# WX0_007_418DL.net
KiCad netlist of a schematic drawn in Altium Designer
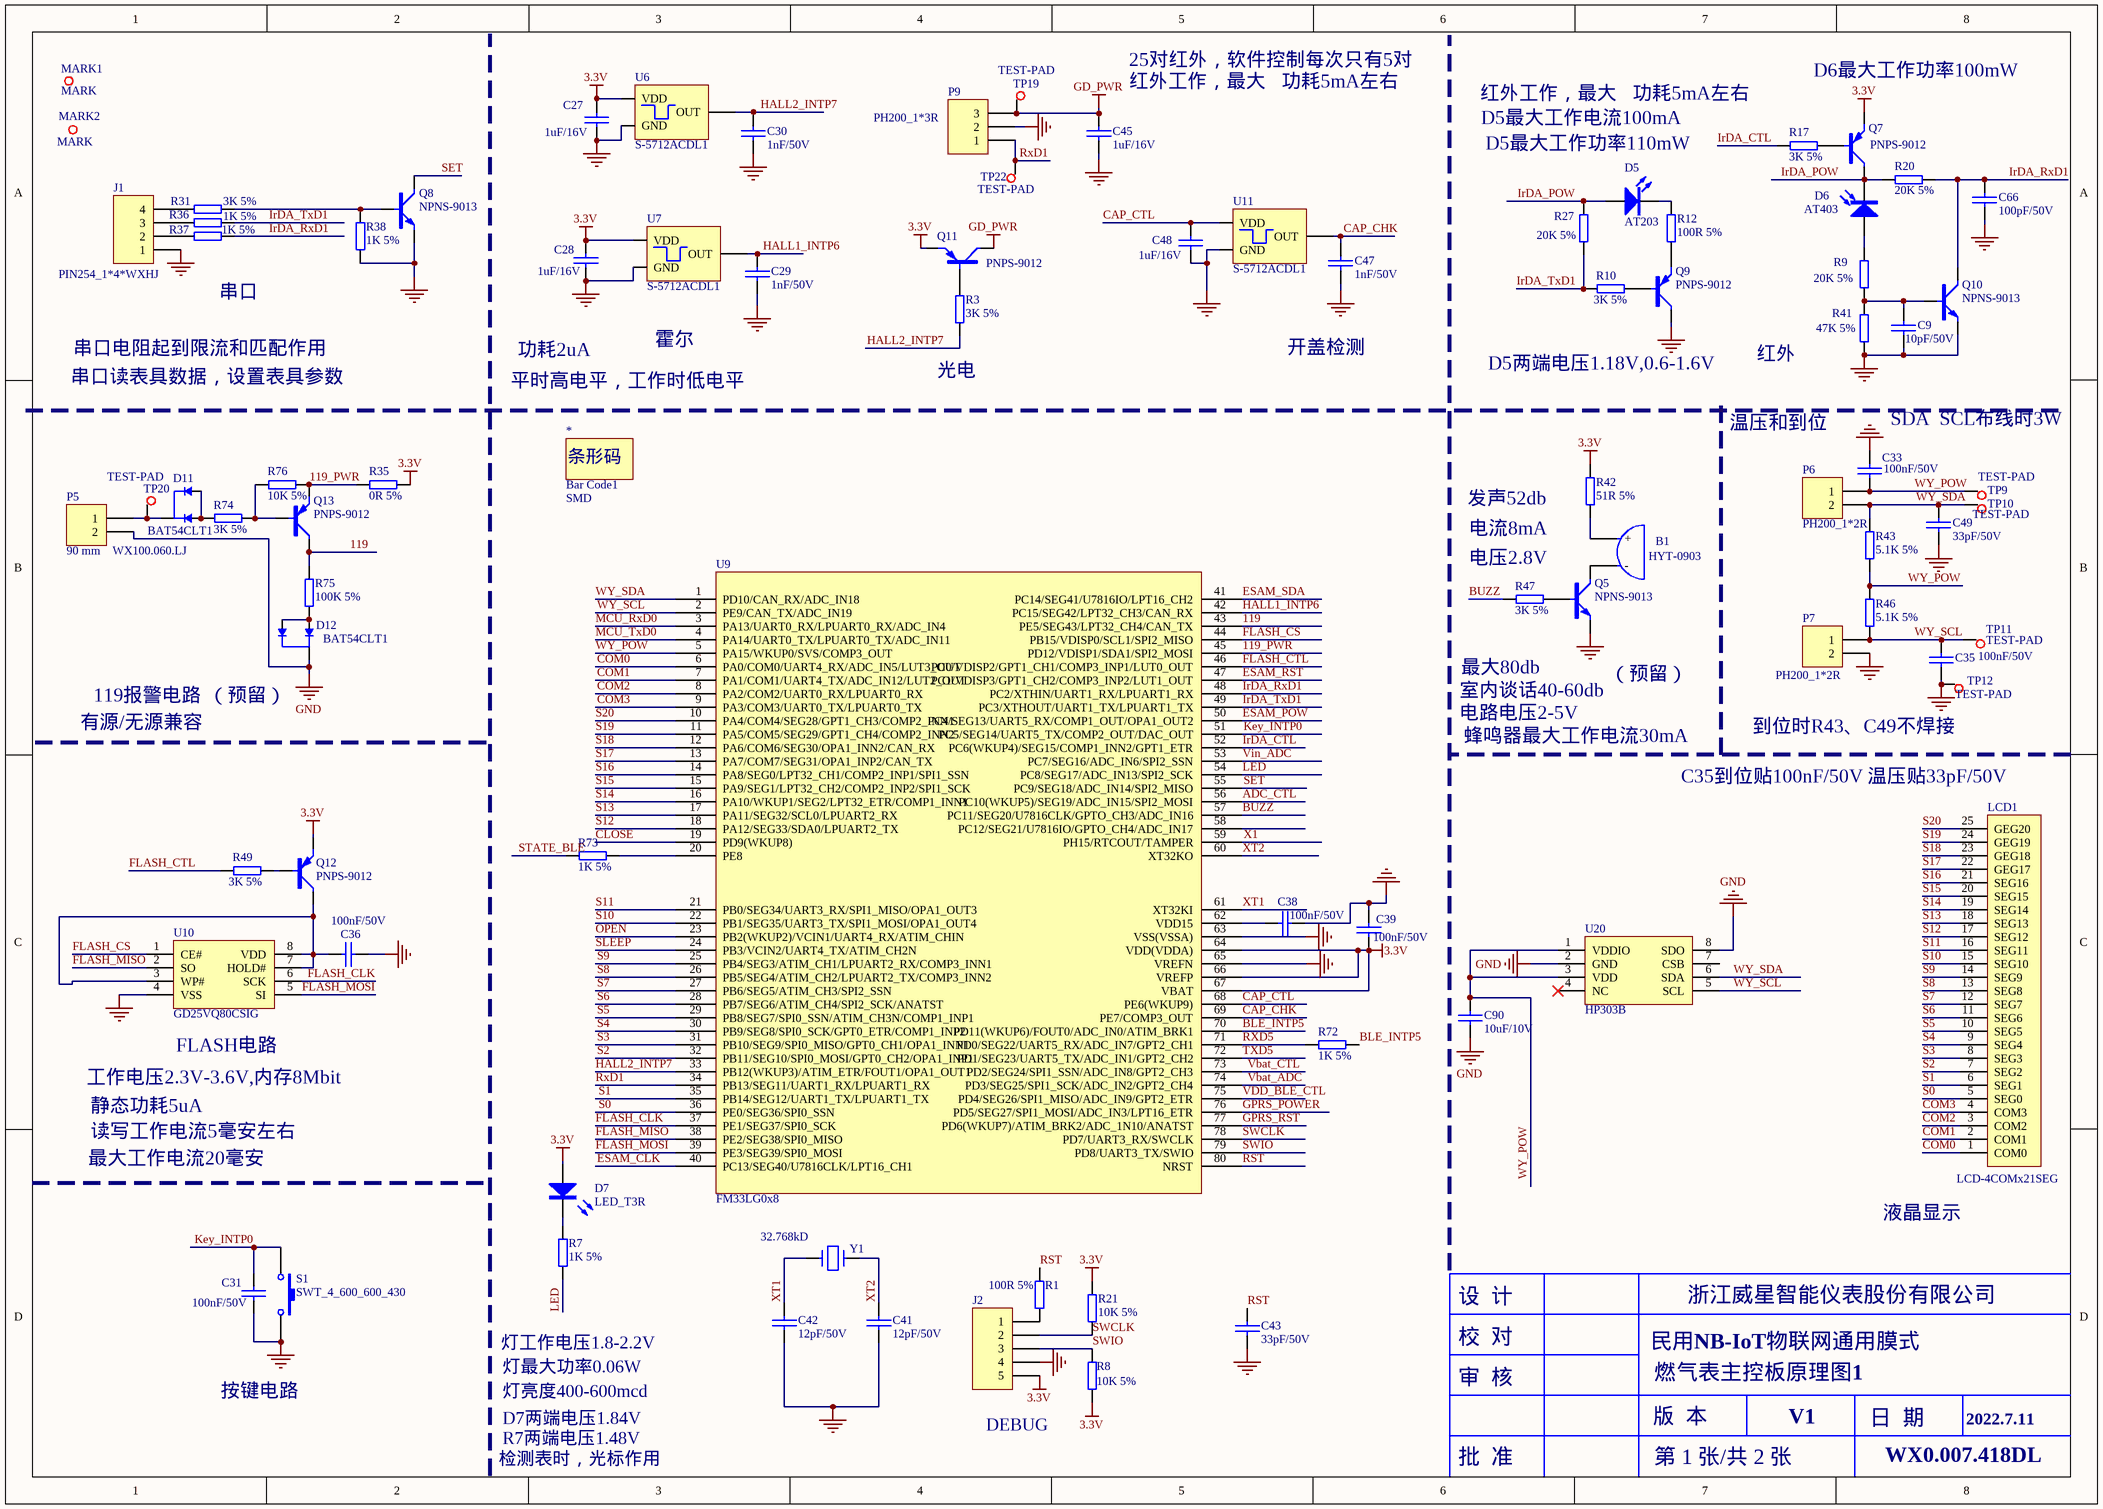
[diagram p0: WX0.007.418DL.SchDoc]

(export (version "E")
  (design (tool "Eeschema 10.0.6"))
  (components
    (comp (ref "*")
      (value "Bar Code1")
      (footprint "Bar Code1")
      (description "条形码 ,填充，无需焊接器件")
      (fields (field (name "PART NUMBER") "AD_WXHJ_Bar Code_02") (field (name "SMD/DIP") "SMD"))
      (libsource (lib "Database_Libs2") (part "05_AD_WXHJ_Bar Code_02"))
    )
    (comp (ref "B1")
      (value "HYT-0903")
      (footprint "HYT-0903")
      (description "直插,直径9mm,高5.5mm,5 V,2 V,30 mA,兴化市华宇电子有限公司,HYT-0903")
      (fields (field (name "PART NUMBER") "1010602-0007"))
      (libsource (lib "Database_Libs2") (part "07_HYT-0903"))
    )
    (comp (ref "C9")
      (value "10pF/50V")
      (footprint "CAP0603")
      (description "10pF,50 V,±5%,0603,X7R,国巨,CC0603JRNPO9BN100")
      (fields (field (name "PART NUMBER") "101020103-0014"))
      (libsource (lib "Database_Libs2") (part "CC03JPO9_10P"))
    )
    (comp (ref "C27")
      (value "1uF/16V")
      (footprint "CAP0603")
      (description "105pF,16 V,±10%,0603,国巨,CC0603KRX7R7BB105")
      (fields (field (name "PART NUMBER") "101020103-0003"))
      (libsource (lib "Database_Libs2") (part "CC03K7R7_1U"))
    )
    (comp (ref "C28")
      (value "1uF/16V")
      (footprint "CAP0603")
      (description "105pF,16 V,±10%,0603,国巨,CC0603KRX7R7BB105")
      (fields (field (name "PART NUMBER") "101020103-0003"))
      (libsource (lib "Database_Libs2") (part "CC03K7R7_1U"))
    )
    (comp (ref "C29")
      (value "1nF/50V")
      (footprint "CAP0603")
      (description "102pF,50 V,±10%,0603,国巨,CC0603KRX7R9BB102")
      (fields (field (name "PART NUMBER") "101020103-0022"))
      (libsource (lib "Database_Libs2") (part "CC03K7R9_1N"))
    )
    (comp (ref "C30")
      (value "1nF/50V")
      (footprint "CAP0603")
      (description "102pF,50 V,±10%,0603,国巨,CC0603KRX7R9BB102")
      (fields (field (name "PART NUMBER") "101020103-0022"))
      (libsource (lib "Database_Libs2") (part "CC03K7R9_1N"))
    )
    (comp (ref "C31")
      (value "100nF/50V")
      (footprint "CAP0603")
      (description "104pF,50 V,±10%,0603,国巨,CC0603KRX7R9BB104")
      (fields (field (name "PART NUMBER") "101020103-0021"))
      (libsource (lib "Database_Libs2") (part "CC03K7R9_100N"))
    )
    (comp (ref "C33")
      (value "100nF/50V")
      (footprint "CAP0603")
      (description "104pF,50 V,±10%,0603,国巨,CC0603KRX7R9BB104")
      (fields (field (name "PART NUMBER") "101020103-0021"))
      (libsource (lib "Database_Libs2") (part "CC03K7R9_100N"))
    )
    (comp (ref "C35")
      (value "100nF/50V")
      (footprint "CAP0603")
      (description "104pF,50 V,±10%,0603,国巨,CC0603KRX7R9BB104")
      (fields (field (name "PART NUMBER") "101020103-0021"))
      (libsource (lib "Database_Libs2") (part "CC03K7R9_100N"))
    )
    (comp (ref "C36")
      (value "100nF/50V")
      (footprint "CAP0603")
      (description "104pF,50 V,±10%,0603,国巨,CC0603KRX7R9BB104")
      (fields (field (name "PART NUMBER") "101020103-0021"))
      (libsource (lib "Database_Libs2") (part "CC03K7R9_100N"))
    )
    (comp (ref "C38")
      (value "100nF/50V")
      (footprint "CAP0603")
      (description "104pF,50 V,±10%,0603,国巨,CC0603KRX7R9BB104")
      (fields (field (name "PART NUMBER") "101020103-0021"))
      (libsource (lib "Database_Libs2") (part "CC03K7R9_100N"))
    )
    (comp (ref "C39")
      (value "100nF/50V")
      (footprint "CAP0603")
      (description "104pF,50 V,±10%,0603,国巨,CC0603KRX7R9BB104")
      (fields (field (name "PART NUMBER") "101020103-0021"))
      (libsource (lib "Database_Libs2") (part "CC03K7R9_100N"))
    )
    (comp (ref "C41")
      (value "12pF/50V")
      (footprint "CAP0603")
      (description "12P,50 V,±5%,0603,国巨,CC0603JRNPO9BN12")
      (fields (field (name "PART NUMBER") "101020103-0005"))
      (libsource (lib "Database_Libs2") (part "CC03JPO9_12P"))
    )
    (comp (ref "C42")
      (value "12pF/50V")
      (footprint "CAP0603")
      (description "12P,50 V,±5%,0603,国巨,CC0603JRNPO9BN12")
      (fields (field (name "PART NUMBER") "101020103-0005"))
      (libsource (lib "Database_Libs2") (part "CC03JPO9_12P"))
    )
    (comp (ref "C43")
      (value "33pF/50V")
      (footprint "CAP0603")
      (description "33pF,50 V,±10%,0603,国巨,CC0603KRNPO9BN33")
      (fields (field (name "PART NUMBER") "101020103-0027"))
      (libsource (lib "Database_Libs2") (part "CC03KPO9_33P"))
    )
    (comp (ref "C45")
      (value "1uF/16V")
      (footprint "CAP0603")
      (description "105pF,16 V,±10%,0603,国巨,CC0603KRX7R7BB105")
      (fields (field (name "PART NUMBER") "101020103-0003"))
      (libsource (lib "Database_Libs2") (part "CC03K7R7_1U"))
    )
    (comp (ref "C47")
      (value "1nF/50V")
      (footprint "CAP0603")
      (description "102pF,50 V,±10%,0603,国巨,CC0603KRX7R9BB102")
      (fields (field (name "PART NUMBER") "101020103-0022"))
      (libsource (lib "Database_Libs2") (part "CC03K7R9_1N"))
    )
    (comp (ref "C48")
      (value "1uF/16V")
      (footprint "CAP0603")
      (description "105pF,16 V,±10%,0603,国巨,CC0603KRX7R7BB105")
      (fields (field (name "PART NUMBER") "101020103-0003"))
      (libsource (lib "Database_Libs2") (part "CC03K7R7_1U"))
    )
    (comp (ref "C49")
      (value "33pF/50V")
      (footprint "CAP0603")
      (description "33pF,50 V,±10%,0603,国巨,CC0603KRNPO9BN33")
      (fields (field (name "PART NUMBER") "101020103-0027"))
      (libsource (lib "Database_Libs2") (part "CC03KPO9_33P"))
    )
    (comp (ref "C66")
      (value "100pF/50V")
      (footprint "CAP0603")
      (description "101pf,50 V,±5%,0603,国巨,CC0603JRNP09BN101")
      (fields (field (name "PART NUMBER") "101020103-0010"))
      (libsource (lib "Database_Libs2") (part "CC03JPO9_101P"))
    )
    (comp (ref "C90")
      (value "10uF/10V")
      (footprint "CAP0603")
      (description "106pF,10 V,±10%,0603,村田,GRM188R61A106KE47D")
      (fields (field (name "PART NUMBER") "101020103-0026"))
      (libsource (lib "Database_Libs2") (part "CC03K5R6_10U"))
    )
    (comp (ref "D5")
      (value "AT203")
      (footprint "IR_254_532_300")
      (description "DIP-2,φ3,插件,红光,上海品观电子有限公司/可得,AT203")
      (fields (field (name "PART NUMBER") "101040102-0010"))
      (libsource (lib "Database_Libs2") (part "01_AT203"))
    )
    (comp (ref "D6")
      (value "AT403")
      (footprint "IR_254_532_300")
      (description "DIP-2,φ3,插件,红光,上海品观电子有限公司/可得,AT403-PD-01")
      (fields (field (name "PART NUMBER") "101040102-0011"))
      (libsource (lib "Database_Libs2") (part "01_AT403"))
    )
    (comp (ref "D7")
      (value "LED_T3R")
      (footprint "LED2_300")
      (description "圆形插件,3mm 圆形,插件,红光,湖北匡通电子有限公司,3BB4HC")
      (fields (field (name "PART NUMBER") "101040102-0001"))
      (libsource (lib "Database_Libs2") (part "01-LED_T3R"))
    )
    (comp (ref "D11")
      (value "BAT54CLT1")
      (footprint "SOT-23")
      (description "BAT54CLT1，SOT23-3,SOT23-3,0.2 A,0.8 V,30 V,安森美,BAT54CLT1")
      (fields (field (name "PART NUMBER") "101040101-0038"))
      (libsource (lib "Database_Libs2") (part "02_BAT54CLT1"))
    )
    (comp (ref "D12")
      (value "BAT54CLT1")
      (footprint "SOT-23")
      (description "BAT54CLT1，SOT23-3,SOT23-3,0.2 A,0.8 V,30 V,安森美,BAT54CLT1")
      (fields (field (name "PART NUMBER") "101040101-0038"))
      (libsource (lib "Database_Libs2") (part "02_BAT54CLT1"))
    )
    (comp (ref "J1")
      (value "PIN254_1*4*WXHJ")
      (footprint "PIN254_1*4*WXHJ")
      (description "1*4 ，Φ1.0 ，2.54mm，直脚,无需焊接器件")
      (fields (field (name "PART NUMBER") "AD_WXHJ_PinHeader_01"))
      (libsource (lib "Database_Libs2") (part "PIN254_1*4*WXHJ"))
    )
    (comp (ref "J2")
      (value "PIN254_1*5*WXHJ")
      (footprint "PIN254_1*5*WXHJ")
      (description "1*5 ，Φ1.0 ，2.54mm，直脚,无需焊接器件")
      (fields (field (name "PART NUMBER") "AD_WXHJ_PinHeader_02"))
      (libsource (lib "Database_Libs2") (part "PIN254_1*5*WXHJ"))
    )
    (comp (ref "LCD1")
      (value "GVH26634A-HPP")
      (footprint "LCD_GVH21861A-HPP")
      (description "GVH26634A-HPP-WG,65mm*23mm,针脚,段码,21,液晶,全透,70 ℃,-20 ℃,安徽金视界光电科技有限公司,GVH26634A-HPP-WG")
      (fields (field (name "PART NUMBER") "1010801-0055") (field (name "SMD/DIP") "LCD-4COMx21SEG"))
      (libsource (lib "Database_Libs2") (part "03_LCD_GVH26634A-HPP"))
    )
    (comp (ref "MARK1")
      (value "MARK")
      (footprint "MARK")
      (description "MARK点")
      (fields (field (name "PART NUMBER") "AD_WXHJ_MARK_01"))
      (libsource (lib "Database_Libs2") (part "MARK"))
    )
    (comp (ref "MARK2")
      (value "MARK")
      (footprint "MARK")
      (description "MARK点")
      (fields (field (name "PART NUMBER") "AD_WXHJ_MARK_01"))
      (libsource (lib "Database_Libs2") (part "MARK"))
    )
    (comp (ref "P5")
      (value "90 mm    WX100.060.LJ")
      (footprint "WXHJ_Connect_01")
      (description "电源连接线")
      (fields (field (name "PART NUMBER") "AD_WXHJ_Connect_01"))
      (libsource (lib "Database_Libs2") (part "WXHJ_Connect_01"))
    )
    (comp (ref "P6")
      (value "PH200_1*2R")
      (footprint "PH200_1*2R")
      (description "2.0-2AW,直插弯座，2PIN，脚间距2mm，带防翘起,公头,单排,2.0-2AW;直插弯座，2PIN,脚间距2mm，带防翘起")
      (fields (field (name "PART NUMBER") "1010902-0105"))
      (libsource (lib "Database_Libs2") (part "PH200_1*2R"))
    )
    (comp (ref "P7")
      (value "PH200_1*2R")
      (footprint "PH200_1*2R")
      (description "2.0-2AW,直插弯座，2PIN，脚间距2mm，带防翘起,公头,单排,2.0-2AW;直插弯座，2PIN,脚间距2mm，带防翘起")
      (fields (field (name "PART NUMBER") "1010902-0105"))
      (libsource (lib "Database_Libs2") (part "PH200_1*2R"))
    )
    (comp (ref "P9")
      (value "PH200_1*3R")
      (footprint "PH200_1*3R")
      (description "2.0-3AW,3PIN，2mm脚间距,公头,单排,2.0-3AW；3PIN，脚间距2mm直插弯座带防翘起")
      (fields (field (name "PART NUMBER") "1010902-0104"))
      (libsource (lib "Database_Libs2") (part "PH200_1*3R"))
    )
    (comp (ref "Q5")
      (value "NPNS-9013")
      (footprint "SOT-23")
      (description "9013,NPN,SOT-23,长电,S9013")
      (fields (field (name "PART NUMBER") "101040201-0002"))
      (libsource (lib "Database_Libs2") (part "03_NPNS-9013"))
    )
    (comp (ref "Q7")
      (value "PNPS-9012")
      (footprint "SOT-23")
      (description "9012,PNP,SOT-23,JCET;长电,S9012")
      (fields (field (name "PART NUMBER") "101040201-0001"))
      (libsource (lib "Database_Libs2") (part "03_PNPS-9012"))
    )
    (comp (ref "Q8")
      (value "NPNS-9013")
      (footprint "SOT-23")
      (description "9013,NPN,SOT-23,长电,S9013")
      (fields (field (name "PART NUMBER") "101040201-0002"))
      (libsource (lib "Database_Libs2") (part "03_NPNS-9013"))
    )
    (comp (ref "Q9")
      (value "PNPS-9012")
      (footprint "SOT-23")
      (description "9012,PNP,SOT-23,JCET;长电,S9012")
      (fields (field (name "PART NUMBER") "101040201-0001"))
      (libsource (lib "Database_Libs2") (part "03_PNPS-9012"))
    )
    (comp (ref "Q10")
      (value "NPNS-9013")
      (footprint "SOT-23")
      (description "9013,NPN,SOT-23,长电,S9013")
      (fields (field (name "PART NUMBER") "101040201-0002"))
      (libsource (lib "Database_Libs2") (part "03_NPNS-9013"))
    )
    (comp (ref "Q11")
      (value "PNPS-9012")
      (footprint "SOT-23")
      (description "9012,PNP,SOT-23,JCET;长电,S9012")
      (fields (field (name "PART NUMBER") "101040201-0001"))
      (libsource (lib "Database_Libs2") (part "03_PNPS-9012"))
    )
    (comp (ref "Q12")
      (value "PNPS-9012")
      (footprint "SOT-23")
      (description "9012,PNP,SOT-23,JCET;长电,S9012")
      (fields (field (name "PART NUMBER") "101040201-0001"))
      (libsource (lib "Database_Libs2") (part "03_PNPS-9012"))
    )
    (comp (ref "Q13")
      (value "PNPS-9012")
      (footprint "SOT-23")
      (description "9012,PNP,SOT-23,JCET;长电,S9012")
      (fields (field (name "PART NUMBER") "101040201-0001"))
      (libsource (lib "Database_Libs2") (part "03_PNPS-9012"))
    )
    (comp (ref "R1")
      (value "100R 5%")
      (footprint "RES0603")
      (description "100R,±5%,1/10W,0603,国巨,RC0603JR-07100RL")
      (fields (field (name "PART NUMBER") "101010103-0022"))
      (libsource (lib "Database_Libs2") (part "RC03J_100R"))
    )
    (comp (ref "R3")
      (value "3K 5%")
      (footprint "RES0603")
      (description "国巨,±5%,0603,,155 ℃,-55 ℃,RC0603JR-073KL,无铅,100 ppm/℃,1/10W,,3K")
      (fields (field (name "PART NUMBER") "101010103-0006"))
      (libsource (lib "Database_Libs2") (part "RC03J_3K"))
    )
    (comp (ref "R7")
      (value "1K 5%")
      (footprint "RES0603")
      (description "1K,±5%,1/10W,0603,国巨,RC0603JR-071KL")
      (fields (field (name "PART NUMBER") "101010103-0008"))
      (libsource (lib "Database_Libs2") (part "RC03J_1K"))
    )
    (comp (ref "R8")
      (value "10K 5%")
      (footprint "RES0603")
      (description "国巨,±5%,0603,,155 ℃,-55 ℃,RC0603JR-0710KL,无铅,200 ppm/℃,1/10W,,10K")
      (fields (field (name "PART NUMBER") "101010103-0003"))
      (libsource (lib "Database_Libs2") (part "RC03J_10K"))
    )
    (comp (ref "R9")
      (value "20K 5%")
      (footprint "RES0603")
      (description "国巨,±5%,0603,,155 ℃,-55 ℃,RC0603JR-0720KL,无铅,200 ppm/℃,1/10W,,20K")
      (fields (field (name "PART NUMBER") "101010103-0004"))
      (libsource (lib "Database_Libs2") (part "RC03J_20K"))
    )
    (comp (ref "R10")
      (value "3K 5%")
      (footprint "RES0603")
      (description "国巨,±5%,0603,,155 ℃,-55 ℃,RC0603JR-073KL,无铅,100 ppm/℃,1/10W,,3K")
      (fields (field (name "PART NUMBER") "101010103-0006"))
      (libsource (lib "Database_Libs2") (part "RC03J_3K"))
    )
    (comp (ref "R12")
      (value "100R 5%")
      (footprint "RES0603")
      (description "100R,±5%,1/10W,0603,国巨,RC0603JR-07100RL")
      (fields (field (name "PART NUMBER") "101010103-0022"))
      (libsource (lib "Database_Libs2") (part "RC03J_100R"))
    )
    (comp (ref "R17")
      (value "3K 5%")
      (footprint "RES0603")
      (description "国巨,±5%,0603,,155 ℃,-55 ℃,RC0603JR-073KL,无铅,100 ppm/℃,1/10W,,3K")
      (fields (field (name "PART NUMBER") "101010103-0006"))
      (libsource (lib "Database_Libs2") (part "RC03J_3K"))
    )
    (comp (ref "R20")
      (value "20K 5%")
      (footprint "RES0603")
      (description "国巨,±5%,0603,,155 ℃,-55 ℃,RC0603JR-0720KL,无铅,200 ppm/℃,1/10W,,20K")
      (fields (field (name "PART NUMBER") "101010103-0004"))
      (libsource (lib "Database_Libs2") (part "RC03J_20K"))
    )
    (comp (ref "R21")
      (value "10K 5%")
      (footprint "RES0603")
      (description "国巨,±5%,0603,,155 ℃,-55 ℃,RC0603JR-0710KL,无铅,200 ppm/℃,1/10W,,10K")
      (fields (field (name "PART NUMBER") "101010103-0003"))
      (libsource (lib "Database_Libs2") (part "RC03J_10K"))
    )
    (comp (ref "R27")
      (value "20K 5%")
      (footprint "RES0603")
      (description "国巨,±5%,0603,,155 ℃,-55 ℃,RC0603JR-0720KL,无铅,200 ppm/℃,1/10W,,20K")
      (fields (field (name "PART NUMBER") "101010103-0004"))
      (libsource (lib "Database_Libs2") (part "RC03J_20K"))
    )
    (comp (ref "R31")
      (value "3K 5%")
      (footprint "RES0603")
      (description "国巨,±5%,0603,,155 ℃,-55 ℃,RC0603JR-073KL,无铅,100 ppm/℃,1/10W,,3K")
      (fields (field (name "PART NUMBER") "101010103-0006"))
      (libsource (lib "Database_Libs2") (part "RC03J_3K"))
    )
    (comp (ref "R35")
      (value "0R 5%")
      (footprint "RES1206")
      (description "0Ω,±5%,1/4W,1206,国巨,RC1206JR-070RL")
      (fields (field (name "PART NUMBER") "101010101-0013"))
      (libsource (lib "Database_Libs2") (part "RC06J_0R"))
    )
    (comp (ref "R36")
      (value "1K 5%")
      (footprint "RES0603")
      (description "1K,±5%,1/10W,0603,国巨,RC0603JR-071KL")
      (fields (field (name "PART NUMBER") "101010103-0008"))
      (libsource (lib "Database_Libs2") (part "RC03J_1K"))
    )
    (comp (ref "R37")
      (value "1K 5%")
      (footprint "RES0603")
      (description "1K,±5%,1/10W,0603,国巨,RC0603JR-071KL")
      (fields (field (name "PART NUMBER") "101010103-0008"))
      (libsource (lib "Database_Libs2") (part "RC03J_1K"))
    )
    (comp (ref "R38")
      (value "1K 5%")
      (footprint "RES0603")
      (description "1K,±5%,1/10W,0603,国巨,RC0603JR-071KL")
      (fields (field (name "PART NUMBER") "101010103-0008"))
      (libsource (lib "Database_Libs2") (part "RC03J_1K"))
    )
    (comp (ref "R41")
      (value "47K 5%")
      (footprint "RES0603")
      (description "47K,±5%,1/10W,0603,国巨,RC0603JR-0747KL")
      (fields (field (name "PART NUMBER") "101010103-0012"))
      (libsource (lib "Database_Libs2") (part "RC03J_47K"))
    )
    (comp (ref "R42")
      (value "51R 5%")
      (footprint "RES0603")
      (description "国巨,±5%,0603,,155 ℃,-55 ℃,RC0603JR-0751RL,无铅,100 ppm/℃,1/10W,,51欧")
      (fields (field (name "PART NUMBER") "101010103-0037"))
      (libsource (lib "Database_Libs2") (part "RC03J_51R"))
    )
    (comp (ref "R43")
      (value "5.1K 5%")
      (footprint "RES0603")
      (description "国巨,±5%,0603,,155 ℃,55 ℃,RC0603JR-075.1KL,无铅,200 ppm/℃,1/10W,,5.1k")
      (fields (field (name "PART NUMBER") "101010103-0015"))
      (libsource (lib "Database_Libs2") (part "RC03J_5.1K"))
    )
    (comp (ref "R46")
      (value "5.1K 5%")
      (footprint "RES0603")
      (description "国巨,±5%,0603,,155 ℃,55 ℃,RC0603JR-075.1KL,无铅,200 ppm/℃,1/10W,,5.1k")
      (fields (field (name "PART NUMBER") "101010103-0015"))
      (libsource (lib "Database_Libs2") (part "RC03J_5.1K"))
    )
    (comp (ref "R47")
      (value "3K 5%")
      (footprint "RES0603")
      (description "国巨,±5%,0603,,155 ℃,-55 ℃,RC0603JR-073KL,无铅,100 ppm/℃,1/10W,,3K")
      (fields (field (name "PART NUMBER") "101010103-0006"))
      (libsource (lib "Database_Libs2") (part "RC03J_3K"))
    )
    (comp (ref "R49")
      (value "3K 5%")
      (footprint "RES0603")
      (description "国巨,±5%,0603,,155 ℃,-55 ℃,RC0603JR-073KL,无铅,100 ppm/℃,1/10W,,3K")
      (fields (field (name "PART NUMBER") "101010103-0006"))
      (libsource (lib "Database_Libs2") (part "RC03J_3K"))
    )
    (comp (ref "R72")
      (value "1K 5%")
      (footprint "RES0603")
      (description "1K,±5%,1/10W,0603,国巨,RC0603JR-071KL")
      (fields (field (name "PART NUMBER") "101010103-0008"))
      (libsource (lib "Database_Libs2") (part "RC03J_1K"))
    )
    (comp (ref "R73")
      (value "1K 5%")
      (footprint "RES0603")
      (description "1K,±5%,1/10W,0603,国巨,RC0603JR-071KL")
      (fields (field (name "PART NUMBER") "101010103-0008"))
      (libsource (lib "Database_Libs2") (part "RC03J_1K"))
    )
    (comp (ref "R74")
      (value "3K 5%")
      (footprint "RES0603")
      (description "国巨,±5%,0603,,155 ℃,-55 ℃,RC0603JR-073KL,无铅,100 ppm/℃,1/10W,,3K")
      (fields (field (name "PART NUMBER") "101010103-0006"))
      (libsource (lib "Database_Libs2") (part "RC03J_3K"))
    )
    (comp (ref "R75")
      (value "100K 5%")
      (footprint "RES0603")
      (description "国巨,±5%,0603,,155 ℃,-55 ℃,RC0603JR-07100KL,无铅,100 ppm/℃,1/10W,,100K")
      (fields (field (name "PART NUMBER") "101010103-0005"))
      (libsource (lib "Database_Libs2") (part "RC03J_100K"))
    )
    (comp (ref "R76")
      (value "10K 5%")
      (footprint "RES0603")
      (description "国巨,±5%,0603,,155 ℃,-55 ℃,RC0603JR-0710KL,无铅,200 ppm/℃,1/10W,,10K")
      (fields (field (name "PART NUMBER") "101010103-0003"))
      (libsource (lib "Database_Libs2") (part "RC03J_10K"))
    )
    (comp (ref "S1")
      (value "SWT_4_600_600_430")
      (footprint "SWT_4_600_600")
      (description "TS-1102,机械轻触,6*6*4.3直插,6*6*4.3直插,乐清市羽欧电子")
      (fields (field (name "PART NUMBER") "1011001-0027"))
      (libsource (lib "Database_Libs2") (part "07_SWT_4_600_600_430"))
    )
    (comp (ref "TP9")
      (value "TEST-PAD")
      (footprint "TEST-PAD")
      (description "单面焊盘测试点")
      (fields (field (name "PART NUMBER") "AD_WXHJ_TEST-PAD_01"))
      (libsource (lib "Database_Libs2") (part "TEST-PAD"))
    )
    (comp (ref "TP10")
      (value "TEST-PAD")
      (footprint "TEST-PAD")
      (description "单面焊盘测试点")
      (fields (field (name "PART NUMBER") "AD_WXHJ_TEST-PAD_01"))
      (libsource (lib "Database_Libs2") (part "TEST-PAD"))
    )
    (comp (ref "TP11")
      (value "TEST-PAD")
      (footprint "TEST-PAD")
      (description "单面焊盘测试点")
      (fields (field (name "PART NUMBER") "AD_WXHJ_TEST-PAD_01"))
      (libsource (lib "Database_Libs2") (part "TEST-PAD"))
    )
    (comp (ref "TP12")
      (value "TEST-PAD")
      (footprint "TEST-PAD")
      (description "单面焊盘测试点")
      (fields (field (name "PART NUMBER") "AD_WXHJ_TEST-PAD_01"))
      (libsource (lib "Database_Libs2") (part "TEST-PAD"))
    )
    (comp (ref "TP19")
      (value "TEST-PAD")
      (footprint "TEST-PAD")
      (description "单面焊盘测试点")
      (fields (field (name "PART NUMBER") "AD_WXHJ_TEST-PAD_01"))
      (libsource (lib "Database_Libs2") (part "TEST-PAD"))
    )
    (comp (ref "TP20")
      (value "TEST-PAD")
      (footprint "TEST-PAD")
      (description "单面焊盘测试点")
      (fields (field (name "PART NUMBER") "AD_WXHJ_TEST-PAD_01"))
      (libsource (lib "Database_Libs2") (part "TEST-PAD"))
    )
    (comp (ref "TP22")
      (value "TEST-PAD")
      (footprint "TEST-PAD")
      (description "单面焊盘测试点")
      (fields (field (name "PART NUMBER") "AD_WXHJ_TEST-PAD_01"))
      (libsource (lib "Database_Libs2") (part "TEST-PAD"))
    )
    (comp (ref "U6")
      (value "S-5712ACDL1")
      (footprint "SOT-23")
      (description "S-5712ACDL1,SOT23-3,3.5 V,1.6 V,2 uA,精工电子,S-5712ACDL1")
      (fields (field (name "PART NUMBER") "1010504-0002"))
      (libsource (lib "Database_Libs2") (part "01_S-5712ACDL1"))
    )
    (comp (ref "U7")
      (value "S-5712ACDL1")
      (footprint "SOT-23")
      (description "S-5712ACDL1,SOT23-3,3.5 V,1.6 V,2 uA,精工电子,S-5712ACDL1")
      (fields (field (name "PART NUMBER") "1010504-0002"))
      (libsource (lib "Database_Libs2") (part "01_S-5712ACDL1"))
    )
    (comp (ref "U9") (value "FM33LG0x8") (footprint "LQFP80") (libsource (lib "FM_MCU") (part "FM33LG0x8")))
    (comp (ref "U10")
      (value "GD25VQ80CSIG")
      (footprint "SOP-8L-200MIL")
      (description "GD25VQ80CSIG,SOP8 208mil,北京兆易创新科技股份有限公司,GD25VQ80CSIG")
      (fields (field (name "PART NUMBER") "101050101-0165"))
      (libsource (lib "Database_Libs2") (part "04_GD25VQ80CSIG"))
    )
    (comp (ref "U11")
      (value "S-5712ACDL1")
      (footprint "SOT-23")
      (description "S-5712ACDL1,SOT23-3,3.5 V,1.6 V,2 uA,精工电子,S-5712ACDL1")
      (fields (field (name "PART NUMBER") "1010504-0002"))
      (libsource (lib "Database_Libs2") (part "01_S-5712ACDL1"))
    )
    (comp (ref "U20") (value "HP303B") (footprint "LGA_8") (libsource (lib "Schlib2") (part "HP303B")))
    (comp (ref "Y1")
      (value "32.768kD")
      (footprint "SMD-3215_2P")
      (fields (field (name "PART NUMBER") "1010601-0020"))
      (libsource (lib "Database_Libs2") (part "04_XTALSG12MD_32.768kD"))
    )
  )
  (nets
    (net (code "1") (name "/119") (class "Default")
      (node (ref "Q13") (pin "3") (pinfunction "C_3") (pintype "passive"))
      (node (ref "R75") (pin "2") (pinfunction "2_2") (pintype "passive"))
      (node (ref "U9") (pin "43") (pinfunction "PE5/SEG43/LPT32_CH4/CAN_TX_43") (pintype "passive"))
    )
    (net (code "2") (name "/119_PWR") (class "Default")
      (node (ref "Q13") (pin "2") (pinfunction "E_2") (pintype "passive"))
      (node (ref "R35") (pin "2") (pinfunction "2_2") (pintype "passive"))
      (node (ref "R76") (pin "1") (pinfunction "1_1") (pintype "passive"))
      (node (ref "U9") (pin "45") (pinfunction "PD12/VDISP1/SDA1/SPI2_MOSI_45") (pintype "passive"))
    )
    (net (code "3") (name "/ADC_CTL") (class "Default")
      (node (ref "U9") (pin "56") (pinfunction "PC10(WKUP5)/SEG19/ADC_IN15/SPI2_MOSI_56") (pintype "passive"))
    )
    (net (code "4") (name "/BLE_INTP5") (class "Default")
      (node (ref "R72") (pin "1") (pinfunction "1_1") (pintype "passive"))
      (node (ref "U9") (pin "70") (pinfunction "PD11(WKUP6)/FOUT0/ADC_IN0/ATIM_BRK1_70") (pintype "passive"))
    )
    (net (code "5") (name "/BUZZ") (class "Default")
      (node (ref "R47") (pin "1") (pinfunction "1_1") (pintype "passive"))
      (node (ref "U9") (pin "57") (pinfunction "PC11/SEG20/U7816CLK/GPTO_CH3/ADC_IN16_57") (pintype "passive"))
    )
    (net (code "6") (name "/CAP_CHK") (class "Default")
      (node (ref "C47") (pin "1") (pinfunction "1_1") (pintype "passive"))
      (node (ref "U11") (pin "2") (pinfunction "OUT_2") (pintype "passive"))
      (node (ref "U9") (pin "69") (pinfunction "PE7/COMP3_OUT_69") (pintype "passive"))
    )
    (net (code "7") (name "/CAP_CTL") (class "Default")
      (node (ref "C48") (pin "1") (pinfunction "1_1") (pintype "passive"))
      (node (ref "U11") (pin "1") (pinfunction "VDD_1") (pintype "passive"))
      (node (ref "U9") (pin "68") (pinfunction "PE6(WKUP9)_68") (pintype "passive"))
    )
    (net (code "8") (name "/CLOSE") (class "Default")
      (node (ref "U9") (pin "19") (pinfunction "PD9(WKUP8)_19") (pintype "passive"))
    )
    (net (code "9") (name "/COM0") (class "Default")
      (node (ref "LCD1") (pin "1") (pinfunction "COM0_1") (pintype "passive"))
      (node (ref "U9") (pin "6") (pinfunction "PA0/COM0/UART4_RX/ADC_IN5/LUT3_OUT_6") (pintype "passive"))
    )
    (net (code "10") (name "/COM1") (class "Default")
      (node (ref "LCD1") (pin "2") (pinfunction "COM1_2") (pintype "passive"))
      (node (ref "U9") (pin "7") (pinfunction "PA1/COM1/UART4_TX/ADC_IN12/LUT2_OUT_7") (pintype "passive"))
    )
    (net (code "11") (name "/COM2") (class "Default")
      (node (ref "LCD1") (pin "3") (pinfunction "COM2_3") (pintype "passive"))
      (node (ref "U9") (pin "8") (pinfunction "PA2/COM2/UART0_RX/LPUART0_RX_8") (pintype "passive"))
    )
    (net (code "12") (name "/COM3") (class "Default")
      (node (ref "LCD1") (pin "4") (pinfunction "COM3_4") (pintype "passive"))
      (node (ref "U9") (pin "9") (pinfunction "PA3/COM3/UART0_TX/LPUART0_TX_9") (pintype "passive"))
    )
    (net (code "13") (name "/ESAM_CLK") (class "Default")
      (node (ref "U9") (pin "40") (pinfunction "PC13/SEG40/U7816CLK/LPT16_CH1_40") (pintype "passive"))
    )
    (net (code "14") (name "/ESAM_POW") (class "Default")
      (node (ref "U9") (pin "50") (pinfunction "PC4/SEG13/UART5_RX/COMP1_OUT/OPA1_OUT2_50") (pintype "passive"))
    )
    (net (code "15") (name "/ESAM_RST") (class "Default")
      (node (ref "U9") (pin "47") (pinfunction "PC1/VDISP3/GPT1_CH2/COMP3_INP2/LUT1_OUT_47") (pintype "passive"))
    )
    (net (code "16") (name "/ESAM_SDA") (class "Default")
      (node (ref "U9") (pin "41") (pinfunction "PC14/SEG41/U7816IO/LPT16_CH2_41") (pintype "passive"))
    )
    (net (code "17") (name "/FLASH_CLK") (class "Default")
      (node (ref "U10") (pin "6") (pinfunction "SCK_6") (pintype "passive"))
      (node (ref "U9") (pin "37") (pinfunction "PE1/SEG37/SPI0_SCK_37") (pintype "passive"))
    )
    (net (code "18") (name "/FLASH_CS") (class "Default")
      (node (ref "U10") (pin "1") (pinfunction "CE#_1") (pintype "passive"))
      (node (ref "U9") (pin "44") (pinfunction "PB15/VDISP0/SCL1/SPI2_MISO_44") (pintype "passive"))
    )
    (net (code "19") (name "/FLASH_CTL") (class "Default")
      (node (ref "R49") (pin "1") (pinfunction "1_1") (pintype "passive"))
      (node (ref "U9") (pin "46") (pinfunction "PC0/VDISP2/GPT1_CH1/COMP3_INP1/LUT0_OUT_46") (pintype "passive"))
    )
    (net (code "20") (name "/FLASH_MISO") (class "Default")
      (node (ref "U10") (pin "2") (pinfunction "SO_2") (pintype "passive"))
      (node (ref "U9") (pin "38") (pinfunction "PE2/SEG38/SPI0_MISO_38") (pintype "passive"))
    )
    (net (code "21") (name "/FLASH_MOSI") (class "Default")
      (node (ref "U10") (pin "5") (pinfunction "SI_5") (pintype "passive"))
      (node (ref "U9") (pin "39") (pinfunction "PE3/SEG39/SPI0_MOSI_39") (pintype "passive"))
    )
    (net (code "22") (name "/GPRS_POWER") (class "Default")
      (node (ref "U9") (pin "76") (pinfunction "PD5/SEG27/SPI1_MOSI/ADC_IN3/LPT16_ETR_76") (pintype "passive"))
    )
    (net (code "23") (name "/GPRS_RST") (class "Default")
      (node (ref "U9") (pin "77") (pinfunction "PD6(WKUP7)/ATIM_BRK2/ADC_1N10/ANATST_77") (pintype "passive"))
    )
    (net (code "24") (name "/HALL1_INTP6") (class "Default")
      (node (ref "C29") (pin "1") (pinfunction "1_1") (pintype "passive"))
      (node (ref "U7") (pin "2") (pinfunction "OUT_2") (pintype "passive"))
      (node (ref "U9") (pin "42") (pinfunction "PC15/SEG42/LPT32_CH3/CAN_RX_42") (pintype "passive"))
    )
    (net (code "25") (name "/HALL2_INTP7") (class "Default")
      (node (ref "C30") (pin "1") (pinfunction "1_1") (pintype "passive"))
      (node (ref "R3") (pin "1") (pinfunction "1_1") (pintype "passive"))
      (node (ref "U6") (pin "2") (pinfunction "OUT_2") (pintype "passive"))
      (node (ref "U9") (pin "33") (pinfunction "PB12(WKUP3)/ATIM_ETR/FOUT1/OPA1_OUT1_33") (pintype "passive"))
    )
    (net (code "26") (name "/IrDA_CTL") (class "Default")
      (node (ref "R17") (pin "1") (pinfunction "1_1") (pintype "passive"))
      (node (ref "U9") (pin "52") (pinfunction "PC6(WKUP4)/SEG15/COMP1_INN2/GPT1_ETR_52") (pintype "passive"))
    )
    (net (code "27") (name "/IrDA_POW") (class "Default")
      (node (ref "D5") (pin "1") (pinfunction "A_1") (pintype "passive"))
      (node (ref "D6") (pin "2") (pinfunction "K_2") (pintype "passive"))
      (node (ref "Q7") (pin "3") (pinfunction "C_3") (pintype "passive"))
      (node (ref "R20") (pin "1") (pinfunction "1_1") (pintype "passive"))
      (node (ref "R27") (pin "2") (pinfunction "2_2") (pintype "passive"))
    )
    (net (code "28") (name "/IrDA_RxD1") (class "Default")
      (node (ref "C66") (pin "1") (pinfunction "1_1") (pintype "passive"))
      (node (ref "Q10") (pin "3") (pinfunction "C_3") (pintype "passive"))
      (node (ref "R20") (pin "2") (pinfunction "2_2") (pintype "passive"))
      (node (ref "R37") (pin "2") (pinfunction "2_2") (pintype "passive"))
      (node (ref "U9") (pin "48") (pinfunction "PC2/XTHIN/UART1_RX/LPUART1_RX_48") (pintype "passive"))
    )
    (net (code "29") (name "/IrDA_TxD1") (class "Default")
      (node (ref "R10") (pin "1") (pinfunction "1_1") (pintype "passive"))
      (node (ref "R27") (pin "1") (pinfunction "1_1") (pintype "passive"))
      (node (ref "R36") (pin "2") (pinfunction "2_2") (pintype "passive"))
      (node (ref "U9") (pin "49") (pinfunction "PC3/XTHOUT/UART1_TX/LPUART1_TX_49") (pintype "passive"))
    )
    (net (code "30") (name "/Key_INTP0") (class "Default")
      (node (ref "C31") (pin "1") (pinfunction "1_1") (pintype "passive"))
      (node (ref "S1") (pin "1") (pinfunction "1_1") (pintype "passive"))
      (node (ref "U9") (pin "51") (pinfunction "PC5/SEG14/UART5_TX/COMP2_OUT/DAC_OUT_51") (pintype "passive"))
    )
    (net (code "31") (name "/LED") (class "Default")
      (node (ref "R7") (pin "1") (pinfunction "1_1") (pintype "passive"))
      (node (ref "U9") (pin "54") (pinfunction "PC8/SEG17/ADC_IN13/SPI2_SCK_54") (pintype "passive"))
    )
    (net (code "32") (name "/MCU_RxD0") (class "Default")
      (node (ref "U9") (pin "3") (pinfunction "PA13/UART0_RX/LPUART0_RX/ADC_IN4_3") (pintype "passive"))
    )
    (net (code "33") (name "/MCU_TxD0") (class "Default")
      (node (ref "U9") (pin "4") (pinfunction "PA14/UART0_TX/LPUART0_TX/ADC_IN11_4") (pintype "passive"))
    )
    (net (code "34") (name "/OPEN") (class "Default")
      (node (ref "U9") (pin "23") (pinfunction "PB2(WKUP2)/VCIN1/UART4_RX/ATIM_CHIN_23") (pintype "passive"))
    )
    (net (code "35") (name "/RST") (class "Default")
      (node (ref "C43") (pin "1") (pinfunction "1_1") (pintype "passive"))
      (node (ref "R1") (pin "1") (pinfunction "1_1") (pintype "passive"))
      (node (ref "U9") (pin "80") (pinfunction "NRST_80") (pintype "passive"))
    )
    (net (code "36") (name "/RXD5") (class "Default")
      (node (ref "R72") (pin "2") (pinfunction "2_2") (pintype "passive"))
      (node (ref "U9") (pin "71") (pinfunction "PD0/SEG22/UART5_RX/ADC_IN7/GPT2_CH1_71") (pintype "passive"))
    )
    (net (code "37") (name "/RxD1") (class "Default")
      (node (ref "P9") (pin "1") (pinfunction "1_1") (pintype "passive"))
      (node (ref "TP22") (pin "1") (pinfunction "1_1") (pintype "passive"))
      (node (ref "U9") (pin "34") (pinfunction "PB13/SEG11/UART1_RX/LPUART1_RX_34") (pintype "passive"))
    )
    (net (code "38") (name "/S0") (class "Default")
      (node (ref "LCD1") (pin "5") (pinfunction "SEG0_5") (pintype "passive"))
      (node (ref "U9") (pin "36") (pinfunction "PE0/SEG36/SPI0_SSN_36") (pintype "passive"))
    )
    (net (code "39") (name "/S1") (class "Default")
      (node (ref "LCD1") (pin "6") (pinfunction "SEG1_6") (pintype "passive"))
      (node (ref "U9") (pin "35") (pinfunction "PB14/SEG12/UART1_TX/LPUART1_TX_35") (pintype "passive"))
    )
    (net (code "40") (name "/S2") (class "Default")
      (node (ref "LCD1") (pin "7") (pinfunction "SEG2_7") (pintype "passive"))
      (node (ref "U9") (pin "32") (pinfunction "PB11/SEG10/SPI0_MOSI/GPT0_CH2/OPA1_INP1_32") (pintype "passive"))
    )
    (net (code "41") (name "/S3") (class "Default")
      (node (ref "LCD1") (pin "8") (pinfunction "SEG3_8") (pintype "passive"))
      (node (ref "U9") (pin "31") (pinfunction "PB10/SEG9/SPI0_MISO/GPT0_CH1/OPA1_INN1_31") (pintype "passive"))
    )
    (net (code "42") (name "/S4") (class "Default")
      (node (ref "LCD1") (pin "9") (pinfunction "SEG4_9") (pintype "passive"))
      (node (ref "U9") (pin "30") (pinfunction "PB9/SEG8/SPI0_SCK/GPT0_ETR/COMP1_INP2_30") (pintype "passive"))
    )
    (net (code "43") (name "/S5") (class "Default")
      (node (ref "LCD1") (pin "10") (pinfunction "SEG5_10") (pintype "passive"))
      (node (ref "U9") (pin "29") (pinfunction "PB8/SEG7/SPI0_SSN/ATIM_CH3N/COMP1_INP1_29") (pintype "passive"))
    )
    (net (code "44") (name "/S6") (class "Default")
      (node (ref "LCD1") (pin "11") (pinfunction "SEG6_11") (pintype "passive"))
      (node (ref "U9") (pin "28") (pinfunction "PB7/SEG6/ATIM_CH4/SPI2_SCK/ANATST_28") (pintype "passive"))
    )
    (net (code "45") (name "/S7") (class "Default")
      (node (ref "LCD1") (pin "12") (pinfunction "SEG7_12") (pintype "passive"))
      (node (ref "U9") (pin "27") (pinfunction "PB6/SEG5/ATIM_CH3/SPI2_SSN_27") (pintype "passive"))
    )
    (net (code "46") (name "/S8") (class "Default")
      (node (ref "LCD1") (pin "13") (pinfunction "SEG8_13") (pintype "passive"))
      (node (ref "U9") (pin "26") (pinfunction "PB5/SEG4/ATIM_CH2/LPUART2_TX/COMP3_INN2_26") (pintype "passive"))
    )
    (net (code "47") (name "/S9") (class "Default")
      (node (ref "LCD1") (pin "14") (pinfunction "SEG9_14") (pintype "passive"))
      (node (ref "U9") (pin "25") (pinfunction "PB4/SEG3/ATIM_CH1/LPUART2_RX/COMP3_INN1_25") (pintype "passive"))
    )
    (net (code "48") (name "/S10") (class "Default")
      (node (ref "LCD1") (pin "15") (pinfunction "SEG10_15") (pintype "passive"))
      (node (ref "U9") (pin "22") (pinfunction "PB1/SEG35/UART3_TX/SPI1_MOSI/OPA1_OUT4_22") (pintype "passive"))
    )
    (net (code "49") (name "/S11") (class "Default")
      (node (ref "LCD1") (pin "16") (pinfunction "SEG11_16") (pintype "passive"))
      (node (ref "U9") (pin "21") (pinfunction "PB0/SEG34/UART3_RX/SPI1_MISO/OPA1_OUT3_21") (pintype "passive"))
    )
    (net (code "50") (name "/S12") (class "Default")
      (node (ref "LCD1") (pin "17") (pinfunction "SEG12_17") (pintype "passive"))
      (node (ref "U9") (pin "18") (pinfunction "PA12/SEG33/SDA0/LPUART2_TX_18") (pintype "passive"))
    )
    (net (code "51") (name "/S13") (class "Default")
      (node (ref "LCD1") (pin "18") (pinfunction "SEG13_18") (pintype "passive"))
      (node (ref "U9") (pin "17") (pinfunction "PA11/SEG32/SCL0/LPUART2_RX_17") (pintype "passive"))
    )
    (net (code "52") (name "/S14") (class "Default")
      (node (ref "LCD1") (pin "19") (pinfunction "SEG14_19") (pintype "passive"))
      (node (ref "U9") (pin "16") (pinfunction "PA10/WKUP1/SEG2/LPT32_ETR/COMP1_INN1_16") (pintype "passive"))
    )
    (net (code "53") (name "/S15") (class "Default")
      (node (ref "LCD1") (pin "20") (pinfunction "SEG15_20") (pintype "passive"))
      (node (ref "U9") (pin "15") (pinfunction "PA9/SEG1/LPT32_CH2/COMP2_INP2/SPI1_SCK_15") (pintype "passive"))
    )
    (net (code "54") (name "/S16") (class "Default")
      (node (ref "LCD1") (pin "21") (pinfunction "SEG16_21") (pintype "passive"))
      (node (ref "U9") (pin "14") (pinfunction "PA8/SEG0/LPT32_CH1/COMP2_INP1/SPI1_SSN_14") (pintype "passive"))
    )
    (net (code "55") (name "/S17") (class "Default")
      (node (ref "LCD1") (pin "22") (pinfunction "GEG17_22") (pintype "passive"))
      (node (ref "U9") (pin "13") (pinfunction "PA7/COM7/SEG31/OPA1_INP2/CAN_TX_13") (pintype "passive"))
    )
    (net (code "56") (name "/S18") (class "Default")
      (node (ref "LCD1") (pin "23") (pinfunction "GEG18_23") (pintype "passive"))
      (node (ref "U9") (pin "12") (pinfunction "PA6/COM6/SEG30/OPA1_INN2/CAN_RX_12") (pintype "passive"))
    )
    (net (code "57") (name "/S19") (class "Default")
      (node (ref "LCD1") (pin "24") (pinfunction "GEG19_24") (pintype "passive"))
      (node (ref "U9") (pin "11") (pinfunction "PA5/COM5/SEG29/GPT1_CH4/COMP2_INN2_11") (pintype "passive"))
    )
    (net (code "58") (name "/S20") (class "Default")
      (node (ref "LCD1") (pin "25") (pinfunction "GEG20_25") (pintype "passive"))
      (node (ref "U9") (pin "10") (pinfunction "PA4/COM4/SEG28/GPT1_CH3/COMP2_INN1_10") (pintype "passive"))
    )
    (net (code "59") (name "/SET") (class "Default")
      (node (ref "Q8") (pin "3") (pinfunction "C_3") (pintype "passive"))
      (node (ref "U9") (pin "55") (pinfunction "PC9/SEG18/ADC_IN14/SPI2_MISO_55") (pintype "passive"))
    )
    (net (code "60") (name "/SLEEP") (class "Default")
      (node (ref "U9") (pin "24") (pinfunction "PB3/VCIN2/UART4_TX/ATIM_CH2N_24") (pintype "passive"))
    )
    (net (code "61") (name "/STATE_BLE") (class "Default")
      (node (ref "R73") (pin "2") (pinfunction "2_2") (pintype "passive"))
    )
    (net (code "62") (name "/SWCLK") (class "Default")
      (node (ref "J2") (pin "2") (pinfunction "2_2") (pintype "passive"))
      (node (ref "R21") (pin "2") (pinfunction "2_2") (pintype "passive"))
      (node (ref "U9") (pin "78") (pinfunction "PD7/UART3_RX/SWCLK_78") (pintype "passive"))
    )
    (net (code "63") (name "/SWIO") (class "Default")
      (node (ref "J2") (pin "3") (pinfunction "3_3") (pintype "passive"))
      (node (ref "R8") (pin "2") (pinfunction "2_2") (pintype "passive"))
      (node (ref "U9") (pin "79") (pinfunction "PD8/UART3_TX/SWIO_79") (pintype "passive"))
    )
    (net (code "64") (name "/TXD5") (class "Default")
      (node (ref "U9") (pin "72") (pinfunction "PD1/SEG23/UART5_TX/ADC_IN1/GPT2_CH2_72") (pintype "passive"))
    )
    (net (code "65") (name "/VDD_BLE_CTL") (class "Default")
      (node (ref "U9") (pin "75") (pinfunction "PD4/SEG26/SPI1_MISO/ADC_IN9/GPT2_ETR_75") (pintype "passive"))
    )
    (net (code "66") (name "/Vbat_ADC") (class "Default")
      (node (ref "U9") (pin "74") (pinfunction "PD3/SEG25/SPI1_SCK/ADC_IN2/GPT2_CH4_74") (pintype "passive"))
    )
    (net (code "67") (name "/Vbat_CTL") (class "Default")
      (node (ref "U9") (pin "73") (pinfunction "PD2/SEG24/SPI1_SSN/ADC_IN8/GPT2_CH3_73") (pintype "passive"))
    )
    (net (code "68") (name "/Vin_ADC") (class "Default")
      (node (ref "U9") (pin "53") (pinfunction "PC7/SEG16/ADC_IN6/SPI2_SSN_53") (pintype "passive"))
    )
    (net (code "69") (name "/WY_POW") (class "Default")
      (node (ref "C33") (pin "2") (pinfunction "2_2") (pintype "passive"))
      (node (ref "C90") (pin "2") (pinfunction "2_2") (pintype "passive"))
      (node (ref "P6") (pin "1") (pinfunction "1_1") (pintype "passive"))
      (node (ref "R43") (pin "1") (pinfunction "1_1") (pintype "passive"))
      (node (ref "R46") (pin "2") (pinfunction "2_2") (pintype "passive"))
      (node (ref "TP9") (pin "1") (pinfunction "1_1") (pintype "passive"))
      (node (ref "U20") (pin "1") (pinfunction "VDDIO_1") (pintype "passive"))
      (node (ref "U20") (pin "3") (pinfunction "VDD_3") (pintype "passive"))
      (node (ref "U9") (pin "5") (pinfunction "PA15/WKUP0/SVS/COMP3_OUT_5") (pintype "passive"))
    )
    (net (code "70") (name "/WY_SCL") (class "Default")
      (node (ref "C35") (pin "1") (pinfunction "1_1") (pintype "passive"))
      (node (ref "P7") (pin "1") (pinfunction "1_1") (pintype "passive"))
      (node (ref "R46") (pin "1") (pinfunction "1_1") (pintype "passive"))
      (node (ref "TP11") (pin "1") (pinfunction "1_1") (pintype "passive"))
      (node (ref "U20") (pin "5") (pinfunction "SCL_5") (pintype "passive"))
      (node (ref "U9") (pin "2") (pinfunction "PE9/CAN_TX/ADC_IN19_2") (pintype "passive"))
    )
    (net (code "71") (name "/WY_SDA") (class "Default")
      (node (ref "C49") (pin "1") (pinfunction "1_1") (pintype "passive"))
      (node (ref "P6") (pin "2") (pinfunction "2_2") (pintype "passive"))
      (node (ref "R43") (pin "2") (pinfunction "2_2") (pintype "passive"))
      (node (ref "TP10") (pin "1") (pinfunction "1_1") (pintype "passive"))
      (node (ref "U20") (pin "6") (pinfunction "SDA_6") (pintype "passive"))
      (node (ref "U9") (pin "1") (pinfunction "PD10/CAN_RX/ADC_IN18_1") (pintype "passive"))
    )
    (net (code "72") (name "/X1") (class "Default")
      (node (ref "U9") (pin "59") (pinfunction "PH15/RTCOUT/TAMPER_59") (pintype "passive"))
    )
    (net (code "73") (name "/XT1") (class "Default")
      (node (ref "C42") (pin "1") (pinfunction "1_1") (pintype "passive"))
      (node (ref "U9") (pin "61") (pinfunction "XT32KI_61") (pintype "passive"))
      (node (ref "Y1") (pin "1") (pinfunction "1_1") (pintype "passive"))
    )
    (net (code "74") (name "/XT2") (class "Default")
      (node (ref "C41") (pin "2") (pinfunction "2_2") (pintype "passive"))
      (node (ref "U9") (pin "60") (pinfunction "XT32KO_60") (pintype "passive"))
      (node (ref "Y1") (pin "2") (pinfunction "2_2") (pintype "passive"))
    )
    (net (code "75") (name "3.3V") (class "Default")
      (node (ref "C27") (pin "1") (pinfunction "1_1") (pintype "passive"))
      (node (ref "C28") (pin "1") (pinfunction "1_1") (pintype "passive"))
      (node (ref "C39") (pin "2") (pinfunction "2_2") (pintype "passive"))
      (node (ref "D7") (pin "1") (pinfunction "1_1") (pintype "passive"))
      (node (ref "J2") (pin "5") (pinfunction "5_5") (pintype "passive"))
      (node (ref "Q11") (pin "2") (pinfunction "E_2") (pintype "passive"))
      (node (ref "Q12") (pin "2") (pinfunction "E_2") (pintype "passive"))
      (node (ref "Q7") (pin "2") (pinfunction "E_2") (pintype "passive"))
      (node (ref "R21") (pin "1") (pinfunction "1_1") (pintype "passive"))
      (node (ref "R35") (pin "1") (pinfunction "1_1") (pintype "passive"))
      (node (ref "R42") (pin "2") (pinfunction "2_2") (pintype "passive"))
      (node (ref "R8") (pin "1") (pinfunction "1_1") (pintype "passive"))
      (node (ref "U6") (pin "1") (pinfunction "VDD_1") (pintype "passive"))
      (node (ref "U7") (pin "1") (pinfunction "VDD_1") (pintype "passive"))
      (node (ref "U9") (pin "64") (pinfunction "VDD(VDDA)_64") (pintype "passive"))
      (node (ref "U9") (pin "66") (pinfunction "VREFP_66") (pintype "passive"))
      (node (ref "U9") (pin "67") (pinfunction "VBAT_67") (pintype "passive"))
    )
    (net (code "76") (name "GD_PWR") (class "Default")
      (node (ref "C45") (pin "1") (pinfunction "1_1") (pintype "passive"))
      (node (ref "P9") (pin "3") (pinfunction "3_3") (pintype "passive"))
      (node (ref "Q11") (pin "3") (pinfunction "C_3") (pintype "passive"))
      (node (ref "TP19") (pin "1") (pinfunction "1_1") (pintype "passive"))
    )
    (net (code "77") (name "GND") (class "Default")
      (node (ref "C27") (pin "2") (pinfunction "2_2") (pintype "passive"))
      (node (ref "C28") (pin "2") (pinfunction "2_2") (pintype "passive"))
      (node (ref "C29") (pin "2") (pinfunction "2_2") (pintype "passive"))
      (node (ref "C30") (pin "2") (pinfunction "2_2") (pintype "passive"))
      (node (ref "C31") (pin "2") (pinfunction "2_2") (pintype "passive"))
      (node (ref "C33") (pin "1") (pinfunction "1_1") (pintype "passive"))
      (node (ref "C35") (pin "2") (pinfunction "2_2") (pintype "passive"))
      (node (ref "C36") (pin "2") (pinfunction "2_2") (pintype "passive"))
      (node (ref "C38") (pin "2") (pinfunction "2_2") (pintype "passive"))
      (node (ref "C39") (pin "1") (pinfunction "1_1") (pintype "passive"))
      (node (ref "C41") (pin "1") (pinfunction "1_1") (pintype "passive"))
      (node (ref "C42") (pin "2") (pinfunction "2_2") (pintype "passive"))
      (node (ref "C43") (pin "2") (pinfunction "2_2") (pintype "passive"))
      (node (ref "C45") (pin "2") (pinfunction "2_2") (pintype "passive"))
      (node (ref "C47") (pin "2") (pinfunction "2_2") (pintype "passive"))
      (node (ref "C48") (pin "2") (pinfunction "2_2") (pintype "passive"))
      (node (ref "C49") (pin "2") (pinfunction "2_2") (pintype "passive"))
      (node (ref "C66") (pin "2") (pinfunction "2_2") (pintype "passive"))
      (node (ref "C9") (pin "2") (pinfunction "2_2") (pintype "passive"))
      (node (ref "C90") (pin "1") (pinfunction "1_1") (pintype "passive"))
      (node (ref "D12") (pin "3") (pinfunction "C_3") (pintype "passive"))
      (node (ref "J1") (pin "1") (pinfunction "1_1") (pintype "passive"))
      (node (ref "J2") (pin "4") (pinfunction "4_4") (pintype "passive"))
      (node (ref "P5") (pin "2") (pinfunction "2_2") (pintype "passive"))
      (node (ref "P7") (pin "2") (pinfunction "2_2") (pintype "passive"))
      (node (ref "P9") (pin "2") (pinfunction "2_2") (pintype "passive"))
      (node (ref "Q10") (pin "2") (pinfunction "E_2") (pintype "passive"))
      (node (ref "Q5") (pin "2") (pinfunction "E_2") (pintype "passive"))
      (node (ref "Q8") (pin "2") (pinfunction "E_2") (pintype "passive"))
      (node (ref "Q9") (pin "3") (pinfunction "C_3") (pintype "passive"))
      (node (ref "R38") (pin "1") (pinfunction "1_1") (pintype "passive"))
      (node (ref "R41") (pin "1") (pinfunction "1_1") (pintype "passive"))
      (node (ref "S1") (pin "2") (pinfunction "2_2") (pintype "passive"))
      (node (ref "TP12") (pin "1") (pinfunction "1_1") (pintype "passive"))
      (node (ref "U10") (pin "4") (pinfunction "VSS_4") (pintype "passive"))
      (node (ref "U11") (pin "3") (pinfunction "GND_3") (pintype "passive"))
      (node (ref "U20") (pin "2") (pinfunction "GND_2") (pintype "passive"))
      (node (ref "U20") (pin "8") (pinfunction "SDO_8") (pintype "passive"))
      (node (ref "U6") (pin "3") (pinfunction "GND_3") (pintype "passive"))
      (node (ref "U7") (pin "3") (pinfunction "GND_3") (pintype "passive"))
      (node (ref "U9") (pin "63") (pinfunction "VSS(VSSA)_63") (pintype "passive"))
      (node (ref "U9") (pin "65") (pinfunction "VREFN_65") (pintype "passive"))
    )
    (net (code "78") (name "Net-(B1-+)") (class "Default")
      (node (ref "B1") (pin "1") (pinfunction "+_1") (pintype "passive"))
      (node (ref "R42") (pin "1") (pinfunction "1_1") (pintype "passive"))
    )
    (net (code "79") (name "Net-(B1--)") (class "Default")
      (node (ref "B1") (pin "2") (pinfunction "-_2") (pintype "passive"))
      (node (ref "Q5") (pin "3") (pinfunction "C_3") (pintype "passive"))
    )
    (net (code "80") (name "Net-(D5-K)") (class "Default")
      (node (ref "D5") (pin "2") (pinfunction "K_2") (pintype "passive"))
      (node (ref "R12") (pin "2") (pinfunction "2_2") (pintype "passive"))
    )
    (net (code "81") (name "Net-(D6-A)") (class "Default")
      (node (ref "D6") (pin "1") (pinfunction "A_1") (pintype "passive"))
      (node (ref "R9") (pin "2") (pinfunction "2_2") (pintype "passive"))
    )
    (net (code "82") (name "Net-(D7-Pad2)") (class "Default")
      (node (ref "D7") (pin "2") (pinfunction "2_2") (pintype "passive"))
      (node (ref "R7") (pin "2") (pinfunction "2_2") (pintype "passive"))
    )
    (net (code "83") (name "Net-(D11-A-Pad1)") (class "Default")
      (node (ref "D11") (pin "1") (pinfunction "A_1") (pintype "passive"))
      (node (ref "D11") (pin "2") (pinfunction "A_2") (pintype "passive"))
      (node (ref "R74") (pin "2") (pinfunction "2_2") (pintype "passive"))
    )
    (net (code "84") (name "Net-(D11-C)") (class "Default")
      (node (ref "D11") (pin "3") (pinfunction "C_3") (pintype "passive"))
      (node (ref "P5") (pin "1") (pinfunction "1_1") (pintype "passive"))
      (node (ref "TP20") (pin "1") (pinfunction "1_1") (pintype "passive"))
    )
    (net (code "85") (name "Net-(D12-A-Pad1)") (class "Default")
      (node (ref "D12") (pin "1") (pinfunction "A_1") (pintype "passive"))
      (node (ref "D12") (pin "2") (pinfunction "A_2") (pintype "passive"))
      (node (ref "R75") (pin "1") (pinfunction "1_1") (pintype "passive"))
    )
    (net (code "86") (name "Net-(J1-Pad2)") (class "Default")
      (node (ref "J1") (pin "2") (pinfunction "2_2") (pintype "passive"))
      (node (ref "R37") (pin "1") (pinfunction "1_1") (pintype "passive"))
    )
    (net (code "87") (name "Net-(J1-Pad3)") (class "Default")
      (node (ref "J1") (pin "3") (pinfunction "3_3") (pintype "passive"))
      (node (ref "R36") (pin "1") (pinfunction "1_1") (pintype "passive"))
    )
    (net (code "88") (name "Net-(J1-Pad4)") (class "Default")
      (node (ref "J1") (pin "4") (pinfunction "4_4") (pintype "passive"))
      (node (ref "R31") (pin "1") (pinfunction "1_1") (pintype "passive"))
    )
    (net (code "89") (name "Net-(J2-Pad1)") (class "Default")
      (node (ref "J2") (pin "1") (pinfunction "1_1") (pintype "passive"))
      (node (ref "R1") (pin "2") (pinfunction "2_2") (pintype "passive"))
    )
    (net (code "90") (name "Net-(Q5-B)") (class "Default")
      (node (ref "Q5") (pin "1") (pinfunction "B_1") (pintype "passive"))
      (node (ref "R47") (pin "2") (pinfunction "2_2") (pintype "passive"))
    )
    (net (code "91") (name "Net-(Q7-B)") (class "Default")
      (node (ref "Q7") (pin "1") (pinfunction "B_1") (pintype "passive"))
      (node (ref "R17") (pin "2") (pinfunction "2_2") (pintype "passive"))
    )
    (net (code "92") (name "Net-(Q8-B)") (class "Default")
      (node (ref "Q8") (pin "1") (pinfunction "B_1") (pintype "passive"))
      (node (ref "R31") (pin "2") (pinfunction "2_2") (pintype "passive"))
      (node (ref "R38") (pin "2") (pinfunction "2_2") (pintype "passive"))
    )
    (net (code "93") (name "Net-(Q9-B)") (class "Default")
      (node (ref "Q9") (pin "1") (pinfunction "B_1") (pintype "passive"))
      (node (ref "R10") (pin "2") (pinfunction "2_2") (pintype "passive"))
    )
    (net (code "94") (name "Net-(Q9-E)") (class "Default")
      (node (ref "Q9") (pin "2") (pinfunction "E_2") (pintype "passive"))
      (node (ref "R12") (pin "1") (pinfunction "1_1") (pintype "passive"))
    )
    (net (code "95") (name "Net-(Q10-B)") (class "Default")
      (node (ref "C9") (pin "1") (pinfunction "1_1") (pintype "passive"))
      (node (ref "Q10") (pin "1") (pinfunction "B_1") (pintype "passive"))
      (node (ref "R41") (pin "2") (pinfunction "2_2") (pintype "passive"))
      (node (ref "R9") (pin "1") (pinfunction "1_1") (pintype "passive"))
    )
    (net (code "96") (name "Net-(Q11-B)") (class "Default")
      (node (ref "Q11") (pin "1") (pinfunction "B_1") (pintype "passive"))
      (node (ref "R3") (pin "2") (pinfunction "2_2") (pintype "passive"))
    )
    (net (code "97") (name "Net-(Q12-B)") (class "Default")
      (node (ref "Q12") (pin "1") (pinfunction "B_1") (pintype "passive"))
      (node (ref "R49") (pin "2") (pinfunction "2_2") (pintype "passive"))
    )
    (net (code "98") (name "Net-(Q12-C)") (class "Default")
      (node (ref "C36") (pin "1") (pinfunction "1_1") (pintype "passive"))
      (node (ref "Q12") (pin "3") (pinfunction "C_3") (pintype "passive"))
      (node (ref "U10") (pin "3") (pinfunction "WP#_3") (pintype "passive"))
      (node (ref "U10") (pin "7") (pinfunction "HOLD#_7") (pintype "passive"))
      (node (ref "U10") (pin "8") (pinfunction "VDD_8") (pintype "passive"))
    )
    (net (code "99") (name "Net-(Q13-B)") (class "Default")
      (node (ref "Q13") (pin "1") (pinfunction "B_1") (pintype "passive"))
      (node (ref "R74") (pin "1") (pinfunction "1_1") (pintype "passive"))
      (node (ref "R76") (pin "2") (pinfunction "2_2") (pintype "passive"))
    )
    (net (code "100") (name "Net-(U9-PE8)") (class "Default")
      (node (ref "R73") (pin "1") (pinfunction "1_1") (pintype "passive"))
      (node (ref "U9") (pin "20") (pinfunction "PE8_20") (pintype "passive"))
    )
    (net (code "101") (name "Net-(U9-VDD15)") (class "Default")
      (node (ref "C38") (pin "1") (pinfunction "1_1") (pintype "passive"))
      (node (ref "U9") (pin "62") (pinfunction "VDD15_62") (pintype "passive"))
    )
    (net (code "102") (name "unconnected-(U9-PC12{slash}SEG21{slash}U7816IO{slash}GPTO_CH4{slash}ADC_IN17-Pad58)") (class "Default")
      (node (ref "U9") (pin "58") (pinfunction "PC12/SEG21/U7816IO/GPTO_CH4/ADC_IN17_58") (pintype "passive"))
    )
    (net (code "103") (name "unconnected-(U20-CSB-Pad7)") (class "Default")
      (node (ref "U20") (pin "7") (pinfunction "CSB_7") (pintype "passive"))
    )
    (net (code "104") (name "unconnected-(U20-NC-Pad4)") (class "Default")
      (node (ref "U20") (pin "4") (pinfunction "NC_4") (pintype "passive+no_connect"))
    )
  )
)
